# Battery_Fan_Board_March_27.net
KiCad netlist of a schematic drawn in Altium Designer
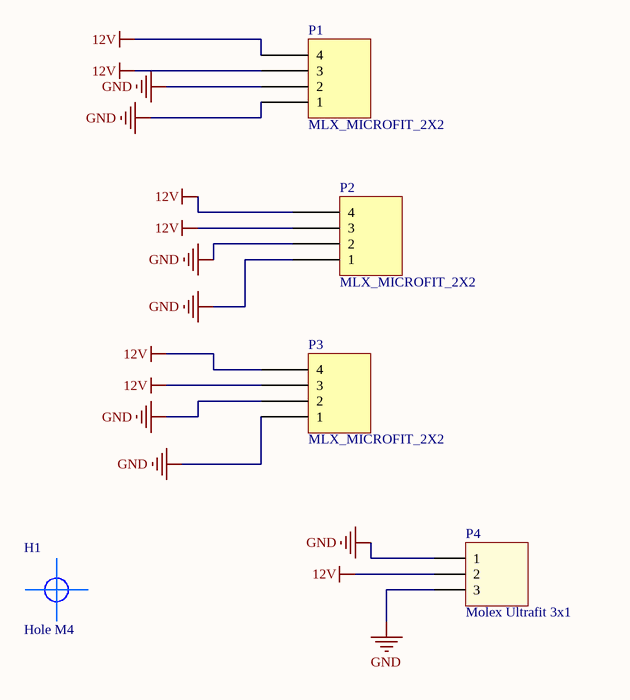
[diagram p0: Battery Fan Board_March 27.SchDoc]

(export (version "E")
  (design (tool "Eeschema 10.0.6"))
  (components
    (comp (ref "H1") (value "Hole M4") (footprint "#10Hole") (libsource (lib "#10Hole") (part "#10Hole")))
    (comp (ref "P1")
      (value "MLX_MICROFIT_2X2")
      (footprint "MLX_MICROFIT_2X2")
      (libsource (lib "Molex Microfit 3.0 2x2") (part "MLX_MICROFIT_2X2"))
    )
    (comp (ref "P2")
      (value "MLX_MICROFIT_2X2")
      (footprint "MLX_MICROFIT_2X2")
      (libsource (lib "Molex Microfit 3.0 2x2") (part "MLX_MICROFIT_2X2"))
    )
    (comp (ref "P3")
      (value "MLX_MICROFIT_2X2")
      (footprint "MLX_MICROFIT_2X2")
      (libsource (lib "Molex Microfit 3.0 2x2") (part "MLX_MICROFIT_2X2"))
    )
    (comp (ref "P4")
      (value "Molex Ultrafit 3x1")
      (footprint "Molex-Ultrafit-3x1")
      (description "Molex Ultrafit 3x1 - 172310-1303")
      (libsource (lib "Molex Ultrafit 3x1 - 172310-1303") (part "Molex-Ultrafit-3x1"))
    )
  )
  (nets
    (net (code "1") (name "12V") (class "Default")
      (node (ref "P1") (pin "3") (pinfunction "3_3") (pintype "passive"))
      (node (ref "P1") (pin "4") (pinfunction "4_4") (pintype "passive"))
      (node (ref "P2") (pin "3") (pinfunction "3_3") (pintype "passive"))
      (node (ref "P2") (pin "4") (pinfunction "4_4") (pintype "passive"))
      (node (ref "P3") (pin "3") (pinfunction "3_3") (pintype "passive"))
      (node (ref "P3") (pin "4") (pinfunction "4_4") (pintype "passive"))
      (node (ref "P4") (pin "2") (pinfunction "2_2") (pintype "passive"))
    )
    (net (code "2") (name "GND") (class "Default")
      (node (ref "P1") (pin "1") (pinfunction "1_1") (pintype "passive"))
      (node (ref "P1") (pin "2") (pinfunction "2_2") (pintype "passive"))
      (node (ref "P2") (pin "1") (pinfunction "1_1") (pintype "passive"))
      (node (ref "P2") (pin "2") (pinfunction "2_2") (pintype "passive"))
      (node (ref "P3") (pin "1") (pinfunction "1_1") (pintype "passive"))
      (node (ref "P3") (pin "2") (pinfunction "2_2") (pintype "passive"))
      (node (ref "P4") (pin "1") (pinfunction "1_1") (pintype "passive"))
      (node (ref "P4") (pin "3") (pinfunction "3_3") (pintype "passive"))
    )
  )
)
